# Ethernet.net
KiCad netlist of a schematic drawn in Altium Designer
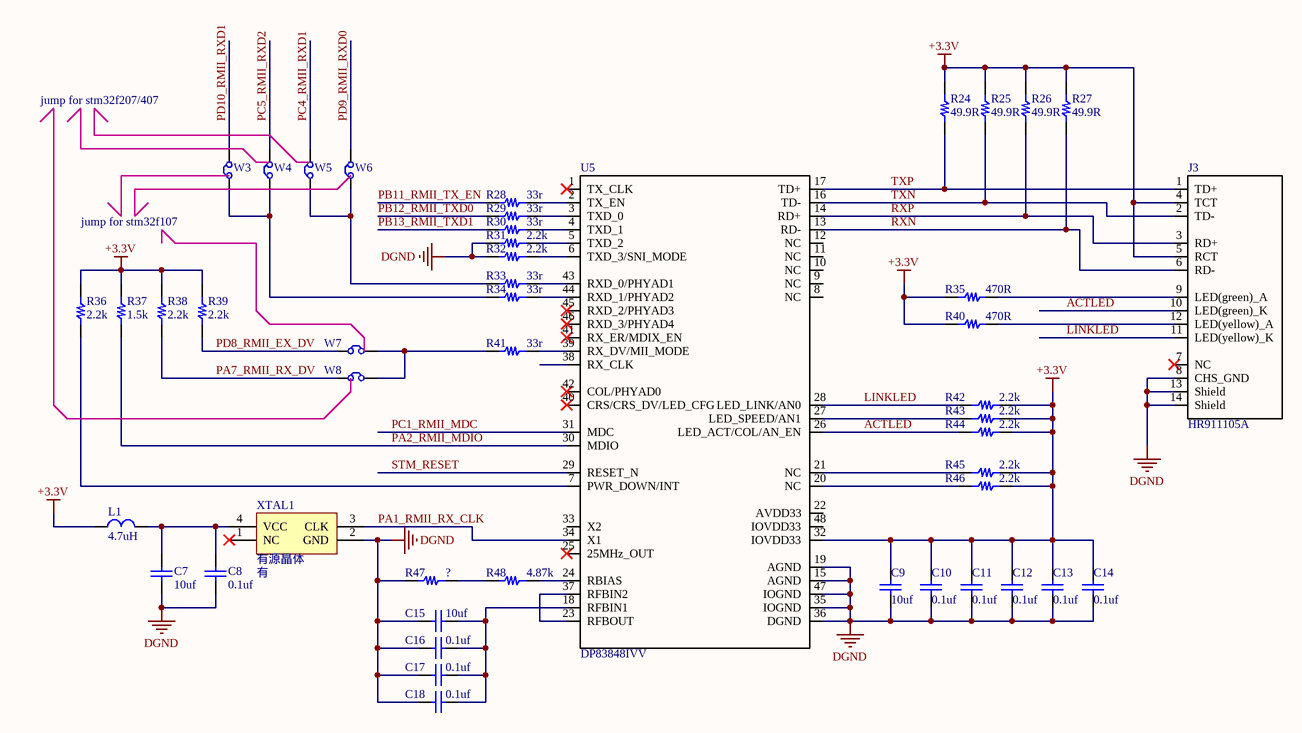
[diagram p0: Ethernet.SchDoc]

(export (version "E")
  (design (tool "Eeschema 10.0.6"))
  (components
    (comp (ref "C7")
      (value "10uf")
      (footprint "0805C")
      (description "贴片电容")
      (fields (field (name "PUBLISHER") "Altium Limited"))
      (libsource (lib "Device_CHT") (part "Cap"))
    )
    (comp (ref "C8")
      (value "0.1uf")
      (footprint "0805C")
      (description "贴片电容")
      (fields (field (name "PUBLISHER") "Altium Limited"))
      (libsource (lib "Device_CHT") (part "Cap"))
    )
    (comp (ref "C9")
      (value "10uf")
      (footprint "0805C")
      (description "贴片电容")
      (fields (field (name "PUBLISHER") "Altium Limited"))
      (libsource (lib "Device_CHT") (part "Cap"))
    )
    (comp (ref "C10")
      (value "0.1uf")
      (footprint "0805C")
      (description "贴片电容")
      (fields (field (name "PUBLISHER") "Altium Limited"))
      (libsource (lib "Device_CHT") (part "Cap"))
    )
    (comp (ref "C11")
      (value "0.1uf")
      (footprint "0805C")
      (description "贴片电容")
      (fields (field (name "PUBLISHER") "Altium Limited"))
      (libsource (lib "Device_CHT") (part "Cap"))
    )
    (comp (ref "C12")
      (value "0.1uf")
      (footprint "0805C")
      (description "贴片电容")
      (fields (field (name "PUBLISHER") "Altium Limited"))
      (libsource (lib "Device_CHT") (part "Cap"))
    )
    (comp (ref "C13")
      (value "0.1uf")
      (footprint "0805C")
      (description "贴片电容")
      (fields (field (name "PUBLISHER") "Altium Limited"))
      (libsource (lib "Device_CHT") (part "Cap"))
    )
    (comp (ref "C14")
      (value "0.1uf")
      (footprint "0805C")
      (description "贴片电容")
      (fields (field (name "PUBLISHER") "Altium Limited"))
      (libsource (lib "Device_CHT") (part "Cap"))
    )
    (comp (ref "C15")
      (value "10uf")
      (footprint "0805C")
      (description "贴片电容")
      (fields (field (name "PUBLISHER") "Altium Limited"))
      (libsource (lib "Device_CHT") (part "Cap"))
    )
    (comp (ref "C16")
      (value "0.1uf")
      (footprint "0805C")
      (description "贴片电容")
      (fields (field (name "PUBLISHER") "Altium Limited"))
      (libsource (lib "Device_CHT") (part "Cap"))
    )
    (comp (ref "C17")
      (value "0.1uf")
      (footprint "0805C")
      (description "贴片电容")
      (fields (field (name "PUBLISHER") "Altium Limited"))
      (libsource (lib "Device_CHT") (part "Cap"))
    )
    (comp (ref "C18")
      (value "0.1uf")
      (footprint "0805C")
      (description "贴片电容")
      (fields (field (name "PUBLISHER") "Altium Limited"))
      (libsource (lib "Device_CHT") (part "Cap"))
    )
    (comp (ref "J3")
      (value "HR911105A")
      (footprint "RJ45-HR911105A")
      (description "带网络变压器的网络接口")
      (libsource (lib "Connector_Veiko") (part "HR911105A"))
    )
    (comp (ref "L1")
      (value "4.7uH")
      (footprint "0805_SmallR")
      (description "电感")
      (fields (field (name "PUBLISHER") "Altium Limited"))
      (libsource (lib "Device_CHT") (part "Inductor"))
    )
    (comp (ref "R24")
      (value "49.9R")
      (footprint "0805_small")
      (description "电阻")
      (fields (field (name "PUBLISHER") "Altium Limited"))
      (libsource (lib "Device_CHT") (part "Res"))
    )
    (comp (ref "R25")
      (value "49.9R")
      (footprint "0805_small")
      (description "电阻")
      (fields (field (name "PUBLISHER") "Altium Limited"))
      (libsource (lib "Device_CHT") (part "Res"))
    )
    (comp (ref "R26")
      (value "49.9R")
      (footprint "0805_small")
      (description "电阻")
      (fields (field (name "PUBLISHER") "Altium Limited"))
      (libsource (lib "Device_CHT") (part "Res"))
    )
    (comp (ref "R27")
      (value "49.9R")
      (footprint "0805_small")
      (description "电阻")
      (fields (field (name "PUBLISHER") "Altium Limited"))
      (libsource (lib "Device_CHT") (part "Res"))
    )
    (comp (ref "R28")
      (value "33r")
      (footprint "0805_small")
      (description "电阻")
      (fields (field (name "PUBLISHER") "Altium Limited"))
      (libsource (lib "Device_CHT") (part "Res"))
    )
    (comp (ref "R29")
      (value "33r")
      (footprint "0805_small")
      (description "电阻")
      (fields (field (name "PUBLISHER") "Altium Limited"))
      (libsource (lib "Device_CHT") (part "Res"))
    )
    (comp (ref "R30")
      (value "33r")
      (footprint "0805_small")
      (description "电阻")
      (fields (field (name "PUBLISHER") "Altium Limited"))
      (libsource (lib "Device_CHT") (part "Res"))
    )
    (comp (ref "R31")
      (value "2.2k")
      (footprint "0805_small")
      (description "电阻")
      (fields (field (name "PUBLISHER") "Altium Limited"))
      (libsource (lib "Device_CHT") (part "Res"))
    )
    (comp (ref "R32")
      (value "2.2k")
      (footprint "0805_small")
      (description "电阻")
      (fields (field (name "PUBLISHER") "Altium Limited"))
      (libsource (lib "Device_CHT") (part "Res"))
    )
    (comp (ref "R33")
      (value "33r")
      (footprint "0805_small")
      (description "电阻")
      (fields (field (name "PUBLISHER") "Altium Limited"))
      (libsource (lib "Device_CHT") (part "Res"))
    )
    (comp (ref "R34")
      (value "33r")
      (footprint "0805_small")
      (description "电阻")
      (fields (field (name "PUBLISHER") "Altium Limited"))
      (libsource (lib "Device_CHT") (part "Res"))
    )
    (comp (ref "R35")
      (value "470R")
      (footprint "0805_small")
      (description "电阻")
      (fields (field (name "PUBLISHER") "Altium Limited"))
      (libsource (lib "Device_CHT") (part "Res"))
    )
    (comp (ref "R36")
      (value "2.2k")
      (footprint "0805_small")
      (description "电阻")
      (fields (field (name "PUBLISHER") "Altium Limited"))
      (libsource (lib "Device_CHT") (part "Res"))
    )
    (comp (ref "R37")
      (value "1.5k")
      (footprint "0805_small")
      (description "电阻")
      (fields (field (name "PUBLISHER") "Altium Limited"))
      (libsource (lib "Device_CHT") (part "Res"))
    )
    (comp (ref "R38")
      (value "2.2k")
      (footprint "0805_small")
      (description "电阻")
      (fields (field (name "PUBLISHER") "Altium Limited"))
      (libsource (lib "Device_CHT") (part "Res"))
    )
    (comp (ref "R39")
      (value "2.2k")
      (footprint "0805_small")
      (description "电阻")
      (fields (field (name "PUBLISHER") "Altium Limited"))
      (libsource (lib "Device_CHT") (part "Res"))
    )
    (comp (ref "R40")
      (value "470R")
      (footprint "0805_small")
      (description "电阻")
      (fields (field (name "PUBLISHER") "Altium Limited"))
      (libsource (lib "Device_CHT") (part "Res"))
    )
    (comp (ref "R41")
      (value "33r")
      (footprint "0805_small")
      (description "电阻")
      (fields (field (name "PUBLISHER") "Altium Limited"))
      (libsource (lib "Device_CHT") (part "Res"))
    )
    (comp (ref "R42")
      (value "2.2k")
      (footprint "0805_small")
      (description "电阻")
      (fields (field (name "PUBLISHER") "Altium Limited"))
      (libsource (lib "Device_CHT") (part "Res"))
    )
    (comp (ref "R43")
      (value "2.2k")
      (footprint "0805_small")
      (description "电阻")
      (fields (field (name "PUBLISHER") "Altium Limited"))
      (libsource (lib "Device_CHT") (part "Res"))
    )
    (comp (ref "R44")
      (value "2.2k")
      (footprint "0805_small")
      (description "电阻")
      (fields (field (name "PUBLISHER") "Altium Limited"))
      (libsource (lib "Device_CHT") (part "Res"))
    )
    (comp (ref "R45")
      (value "2.2k")
      (footprint "0805_small")
      (description "电阻")
      (fields (field (name "PUBLISHER") "Altium Limited"))
      (libsource (lib "Device_CHT") (part "Res"))
    )
    (comp (ref "R46")
      (value "2.2k")
      (footprint "0805_small")
      (description "电阻")
      (fields (field (name "PUBLISHER") "Altium Limited"))
      (libsource (lib "Device_CHT") (part "Res"))
    )
    (comp (ref "R47")
      (value "?")
      (footprint "0805_small")
      (description "电阻")
      (fields (field (name "PUBLISHER") "Altium Limited"))
      (libsource (lib "Device_CHT") (part "Res"))
    )
    (comp (ref "R48")
      (value "4.87k")
      (footprint "0805_small")
      (description "电阻")
      (fields (field (name "PUBLISHER") "Altium Limited"))
      (libsource (lib "Device_CHT") (part "Res"))
    )
    (comp (ref "U5")
      (value "DP83848IVV")
      (footprint "LQFP-48")
      (description "DP83848 PHY")
      (libsource (lib "Device_CHT") (part "DP83848IVV"))
    )
    (comp (ref "W3")
      (value "~")
      (footprint "0603_jump_Pad")
      (description "Jumper Wire")
      (fields (field (name "PUBLISHER") "Altium Limited"))
      (libsource (lib "Connector_Veiko") (part "Jumper"))
    )
    (comp (ref "W4")
      (value "~")
      (footprint "0603_jump_Pad")
      (description "Jumper Wire")
      (fields (field (name "PUBLISHER") "Altium Limited"))
      (libsource (lib "Connector_Veiko") (part "Jumper"))
    )
    (comp (ref "W5")
      (value "~")
      (footprint "0603_jump_Pad")
      (description "Jumper Wire")
      (fields (field (name "PUBLISHER") "Altium Limited"))
      (libsource (lib "Connector_Veiko") (part "Jumper"))
    )
    (comp (ref "W6")
      (value "~")
      (footprint "0603_jump_Pad")
      (description "Jumper Wire")
      (fields (field (name "PUBLISHER") "Altium Limited"))
      (libsource (lib "Connector_Veiko") (part "Jumper"))
    )
    (comp (ref "W7")
      (value "~")
      (footprint "0603_jump_Pad")
      (description "Jumper Wire")
      (fields (field (name "PUBLISHER") "Altium Limited"))
      (libsource (lib "Connector_Veiko") (part "Jumper"))
    )
    (comp (ref "W8")
      (value "~")
      (footprint "0603_jump_Pad")
      (description "Jumper Wire")
      (fields (field (name "PUBLISHER") "Altium Limited"))
      (libsource (lib "Connector_Veiko") (part "Jumper"))
    )
    (comp (ref "XTAL1")
      (value "有源晶体")
      (footprint "贴片有源晶体")
      (fields (field (name "ALTIUM_UNNAMED_1") "有"))
      (libsource (lib "Device_CHT") (part "有源晶体"))
    )
  )
  (nets
    (net (code "1") (name "+3.3V") (class "Default")
      (node (ref "C10") (pin "1") (pinfunction "1_1") (pintype "passive"))
      (node (ref "C11") (pin "1") (pinfunction "1_1") (pintype "passive"))
      (node (ref "C12") (pin "1") (pinfunction "1_1") (pintype "passive"))
      (node (ref "C13") (pin "1") (pinfunction "1_1") (pintype "passive"))
      (node (ref "C14") (pin "1") (pinfunction "1_1") (pintype "passive"))
      (node (ref "C9") (pin "1") (pinfunction "1_1") (pintype "passive"))
      (node (ref "J3") (pin "4") (pinfunction "TCT_4") (pintype "passive"))
      (node (ref "J3") (pin "5") (pinfunction "RCT_5") (pintype "passive"))
      (node (ref "L1") (pin "1") (pinfunction "1_1") (pintype "passive"))
      (node (ref "R24") (pin "1") (pinfunction "1_1") (pintype "passive"))
      (node (ref "R25") (pin "1") (pinfunction "1_1") (pintype "passive"))
      (node (ref "R26") (pin "1") (pinfunction "1_1") (pintype "passive"))
      (node (ref "R27") (pin "1") (pinfunction "1_1") (pintype "passive"))
      (node (ref "R35") (pin "1") (pinfunction "1_1") (pintype "passive"))
      (node (ref "R36") (pin "1") (pinfunction "1_1") (pintype "passive"))
      (node (ref "R37") (pin "1") (pinfunction "1_1") (pintype "passive"))
      (node (ref "R38") (pin "1") (pinfunction "1_1") (pintype "passive"))
      (node (ref "R39") (pin "1") (pinfunction "1_1") (pintype "passive"))
      (node (ref "R40") (pin "1") (pinfunction "1_1") (pintype "passive"))
      (node (ref "R42") (pin "2") (pinfunction "2_2") (pintype "passive"))
      (node (ref "R43") (pin "2") (pinfunction "2_2") (pintype "passive"))
      (node (ref "R44") (pin "2") (pinfunction "2_2") (pintype "passive"))
      (node (ref "R45") (pin "2") (pinfunction "2_2") (pintype "passive"))
      (node (ref "R46") (pin "2") (pinfunction "2_2") (pintype "passive"))
      (node (ref "U5") (pin "32") (pinfunction "IOVDD33_32") (pintype "passive"))
    )
    (net (code "2") (name "/ACTLED") (class "Default")
      (node (ref "J3") (pin "10") (pinfunction "LED(green)_K_10") (pintype "passive"))
      (node (ref "R44") (pin "1") (pinfunction "1_1") (pintype "passive"))
      (node (ref "U5") (pin "26") (pinfunction "LED_ACT/COL/AN_EN_26") (pintype "passive"))
    )
    (net (code "3") (name "/LINKLED") (class "Default")
      (node (ref "J3") (pin "11") (pinfunction "LED(yellow)_K_11") (pintype "passive"))
      (node (ref "R42") (pin "1") (pinfunction "1_1") (pintype "passive"))
      (node (ref "U5") (pin "28") (pinfunction "LED_LINK/AN0_28") (pintype "passive"))
    )
    (net (code "4") (name "/PA1_RMII_RX_CLK") (class "Default")
      (node (ref "U5") (pin "34") (pinfunction "X1_34") (pintype "passive"))
      (node (ref "XTAL1") (pin "3") (pinfunction "CLK_3") (pintype "passive"))
    )
    (net (code "5") (name "/PA2_RMII_MDIO") (class "Default")
      (node (ref "R37") (pin "2") (pinfunction "2_2") (pintype "passive"))
      (node (ref "U5") (pin "30") (pinfunction "MDIO_30") (pintype "passive"))
    )
    (net (code "6") (name "/PA7_RMII_RX_DV") (class "Default")
      (node (ref "R38") (pin "2") (pinfunction "2_2") (pintype "passive"))
      (node (ref "W8") (pin "1") (pinfunction "C1_1") (pintype "passive"))
    )
    (net (code "7") (name "/PB11_RMII_TX_EN") (class "Default")
      (node (ref "R28") (pin "2") (pinfunction "2_2") (pintype "passive"))
    )
    (net (code "8") (name "/PB12_RMII_TXD0") (class "Default")
      (node (ref "R29") (pin "2") (pinfunction "2_2") (pintype "passive"))
    )
    (net (code "9") (name "/PB13_RMII_TXD1") (class "Default")
      (node (ref "R30") (pin "2") (pinfunction "2_2") (pintype "passive"))
    )
    (net (code "10") (name "/PC1_RMII_MDC") (class "Default")
      (node (ref "U5") (pin "31") (pinfunction "MDC_31") (pintype "passive"))
    )
    (net (code "11") (name "/PC4_RMII_RXD1") (class "Default")
      (node (ref "W5") (pin "2") (pinfunction "C2_2") (pintype "passive"))
    )
    (net (code "12") (name "/PC5_RMII_RXD2") (class "Default")
      (node (ref "W4") (pin "2") (pinfunction "C2_2") (pintype "passive"))
    )
    (net (code "13") (name "/PD8_RMII_EX_DV") (class "Default")
      (node (ref "R39") (pin "2") (pinfunction "2_2") (pintype "passive"))
      (node (ref "W7") (pin "1") (pinfunction "C1_1") (pintype "passive"))
    )
    (net (code "14") (name "/PD9_RMII_RXD0") (class "Default")
      (node (ref "W6") (pin "2") (pinfunction "C2_2") (pintype "passive"))
    )
    (net (code "15") (name "/PD10_RMII_RXD1") (class "Default")
      (node (ref "W3") (pin "2") (pinfunction "C2_2") (pintype "passive"))
    )
    (net (code "16") (name "/RXN") (class "Default")
      (node (ref "J3") (pin "6") (pinfunction "RD-_6") (pintype "passive"))
      (node (ref "R27") (pin "2") (pinfunction "2_2") (pintype "passive"))
      (node (ref "U5") (pin "13") (pinfunction "RD-_13") (pintype "passive"))
    )
    (net (code "17") (name "/RXP") (class "Default")
      (node (ref "J3") (pin "3") (pinfunction "RD+_3") (pintype "passive"))
      (node (ref "R26") (pin "2") (pinfunction "2_2") (pintype "passive"))
      (node (ref "U5") (pin "14") (pinfunction "RD+_14") (pintype "passive"))
    )
    (net (code "18") (name "/STM_RESET") (class "Default")
      (node (ref "U5") (pin "29") (pinfunction "RESET_N_29") (pintype "passive"))
    )
    (net (code "19") (name "/TXN") (class "Default")
      (node (ref "J3") (pin "2") (pinfunction "TD-_2") (pintype "passive"))
      (node (ref "R25") (pin "2") (pinfunction "2_2") (pintype "passive"))
      (node (ref "U5") (pin "16") (pinfunction "TD-_16") (pintype "passive"))
    )
    (net (code "20") (name "/TXP") (class "Default")
      (node (ref "J3") (pin "1") (pinfunction "TD+_1") (pintype "passive"))
      (node (ref "R24") (pin "2") (pinfunction "2_2") (pintype "passive"))
      (node (ref "U5") (pin "17") (pinfunction "TD+_17") (pintype "passive"))
    )
    (net (code "21") (name "DGND") (class "Default")
      (node (ref "C10") (pin "2") (pinfunction "2_2") (pintype "passive"))
      (node (ref "C11") (pin "2") (pinfunction "2_2") (pintype "passive"))
      (node (ref "C12") (pin "2") (pinfunction "2_2") (pintype "passive"))
      (node (ref "C13") (pin "2") (pinfunction "2_2") (pintype "passive"))
      (node (ref "C14") (pin "2") (pinfunction "2_2") (pintype "passive"))
      (node (ref "C15") (pin "2") (pinfunction "2_2") (pintype "passive"))
      (node (ref "C16") (pin "2") (pinfunction "2_2") (pintype "passive"))
      (node (ref "C17") (pin "2") (pinfunction "2_2") (pintype "passive"))
      (node (ref "C18") (pin "2") (pinfunction "2_2") (pintype "passive"))
      (node (ref "C7") (pin "2") (pinfunction "2_2") (pintype "passive"))
      (node (ref "C8") (pin "2") (pinfunction "2_2") (pintype "passive"))
      (node (ref "C9") (pin "2") (pinfunction "2_2") (pintype "passive"))
      (node (ref "J3") (pin "13") (pinfunction "Shield_13") (pintype "passive"))
      (node (ref "J3") (pin "14") (pinfunction "Shield_14") (pintype "passive"))
      (node (ref "J3") (pin "8") (pinfunction "CHS_GND_8") (pintype "passive"))
      (node (ref "R31") (pin "2") (pinfunction "2_2") (pintype "passive"))
      (node (ref "R32") (pin "2") (pinfunction "2_2") (pintype "passive"))
      (node (ref "R47") (pin "2") (pinfunction "2_2") (pintype "passive"))
      (node (ref "U5") (pin "15") (pinfunction "AGND_15") (pintype "passive"))
      (node (ref "U5") (pin "19") (pinfunction "AGND_19") (pintype "passive"))
      (node (ref "U5") (pin "35") (pinfunction "IOGND_35") (pintype "passive"))
      (node (ref "U5") (pin "36") (pinfunction "DGND_36") (pintype "passive"))
      (node (ref "U5") (pin "47") (pinfunction "IOGND_47") (pintype "passive"))
      (node (ref "XTAL1") (pin "2") (pinfunction "GND_2") (pintype "passive"))
    )
    (net (code "22") (name "Net-(J3-LED(green)_A)") (class "Default")
      (node (ref "J3") (pin "9") (pinfunction "LED(green)_A_9") (pintype "passive"))
      (node (ref "R35") (pin "2") (pinfunction "2_2") (pintype "passive"))
    )
    (net (code "23") (name "Net-(J3-LED(yellow)_A)") (class "Default")
      (node (ref "J3") (pin "12") (pinfunction "LED(yellow)_A_12") (pintype "passive"))
      (node (ref "R40") (pin "2") (pinfunction "2_2") (pintype "passive"))
    )
    (net (code "24") (name "Net-(R45-Pad1)") (class "Default")
      (node (ref "R45") (pin "1") (pinfunction "1_1") (pintype "passive"))
      (node (ref "U5") (pin "21") (pinfunction "NC_21") (pintype "passive"))
    )
    (net (code "25") (name "Net-(R46-Pad1)") (class "Default")
      (node (ref "R46") (pin "1") (pinfunction "1_1") (pintype "passive"))
      (node (ref "U5") (pin "20") (pinfunction "NC_20") (pintype "passive"))
    )
    (net (code "26") (name "Net-(R47-Pad1)") (class "Default")
      (node (ref "R47") (pin "1") (pinfunction "1_1") (pintype "passive"))
      (node (ref "R48") (pin "2") (pinfunction "2_2") (pintype "passive"))
    )
    (net (code "27") (name "Net-(U5-LED_SPEED{slash}AN1)") (class "Default")
      (node (ref "R43") (pin "1") (pinfunction "1_1") (pintype "passive"))
      (node (ref "U5") (pin "27") (pinfunction "LED_SPEED/AN1_27") (pintype "passive"))
    )
    (net (code "28") (name "Net-(U5-PWR_DOWN{slash}INT)") (class "Default")
      (node (ref "R36") (pin "2") (pinfunction "2_2") (pintype "passive"))
      (node (ref "U5") (pin "7") (pinfunction "PWR_DOWN/INT_7") (pintype "passive"))
    )
    (net (code "29") (name "Net-(U5-RBIAS)") (class "Default")
      (node (ref "R48") (pin "1") (pinfunction "1_1") (pintype "passive"))
      (node (ref "U5") (pin "24") (pinfunction "RBIAS_24") (pintype "passive"))
    )
    (net (code "30") (name "Net-(U5-RFBIN1)") (class "Default")
      (node (ref "C15") (pin "1") (pinfunction "1_1") (pintype "passive"))
      (node (ref "C16") (pin "1") (pinfunction "1_1") (pintype "passive"))
      (node (ref "C17") (pin "1") (pinfunction "1_1") (pintype "passive"))
      (node (ref "C18") (pin "1") (pinfunction "1_1") (pintype "passive"))
      (node (ref "U5") (pin "18") (pinfunction "RFBIN1_18") (pintype "passive"))
    )
    (net (code "31") (name "Net-(U5-RFBIN2)") (class "Default")
      (node (ref "U5") (pin "23") (pinfunction "RFBOUT_23") (pintype "passive"))
      (node (ref "U5") (pin "37") (pinfunction "RFBIN2_37") (pintype "passive"))
    )
    (net (code "32") (name "Net-(U5-RXD_0{slash}PHYAD1)") (class "Default")
      (node (ref "R33") (pin "1") (pinfunction "1_1") (pintype "passive"))
      (node (ref "U5") (pin "43") (pinfunction "RXD_0/PHYAD1_43") (pintype "passive"))
    )
    (net (code "33") (name "Net-(U5-RXD_1{slash}PHYAD2)") (class "Default")
      (node (ref "R34") (pin "1") (pinfunction "1_1") (pintype "passive"))
      (node (ref "U5") (pin "44") (pinfunction "RXD_1/PHYAD2_44") (pintype "passive"))
    )
    (net (code "34") (name "Net-(U5-RX_DV{slash}MII_MODE)") (class "Default")
      (node (ref "R41") (pin "1") (pinfunction "1_1") (pintype "passive"))
      (node (ref "U5") (pin "39") (pinfunction "RX_DV/MII_MODE_39") (pintype "passive"))
    )
    (net (code "35") (name "Net-(U5-TXD_0)") (class "Default")
      (node (ref "R29") (pin "1") (pinfunction "1_1") (pintype "passive"))
      (node (ref "U5") (pin "3") (pinfunction "TXD_0_3") (pintype "passive"))
    )
    (net (code "36") (name "Net-(U5-TXD_1)") (class "Default")
      (node (ref "R30") (pin "1") (pinfunction "1_1") (pintype "passive"))
      (node (ref "U5") (pin "4") (pinfunction "TXD_1_4") (pintype "passive"))
    )
    (net (code "37") (name "Net-(U5-TXD_2)") (class "Default")
      (node (ref "R31") (pin "1") (pinfunction "1_1") (pintype "passive"))
      (node (ref "U5") (pin "5") (pinfunction "TXD_2_5") (pintype "passive"))
    )
    (net (code "38") (name "Net-(U5-TXD_3{slash}SNI_MODE)") (class "Default")
      (node (ref "R32") (pin "1") (pinfunction "1_1") (pintype "passive"))
      (node (ref "U5") (pin "6") (pinfunction "TXD_3/SNI_MODE_6") (pintype "passive"))
    )
    (net (code "39") (name "Net-(U5-TX_EN)") (class "Default")
      (node (ref "R28") (pin "1") (pinfunction "1_1") (pintype "passive"))
      (node (ref "U5") (pin "2") (pinfunction "TX_EN_2") (pintype "passive"))
    )
    (net (code "40") (name "Net-(W3-C1)") (class "Default")
      (node (ref "R34") (pin "2") (pinfunction "2_2") (pintype "passive"))
      (node (ref "W3") (pin "1") (pinfunction "C1_1") (pintype "passive"))
      (node (ref "W4") (pin "1") (pinfunction "C1_1") (pintype "passive"))
    )
    (net (code "41") (name "Net-(W5-C1)") (class "Default")
      (node (ref "R33") (pin "2") (pinfunction "2_2") (pintype "passive"))
      (node (ref "W5") (pin "1") (pinfunction "C1_1") (pintype "passive"))
      (node (ref "W6") (pin "1") (pinfunction "C1_1") (pintype "passive"))
    )
    (net (code "42") (name "Net-(W7-C2)") (class "Default")
      (node (ref "R41") (pin "2") (pinfunction "2_2") (pintype "passive"))
      (node (ref "W7") (pin "2") (pinfunction "C2_2") (pintype "passive"))
      (node (ref "W8") (pin "2") (pinfunction "C2_2") (pintype "passive"))
    )
    (net (code "43") (name "Net-(XTAL1-VCC)") (class "Default")
      (node (ref "C7") (pin "1") (pinfunction "1_1") (pintype "passive"))
      (node (ref "C8") (pin "1") (pinfunction "1_1") (pintype "passive"))
      (node (ref "L1") (pin "2") (pinfunction "2_2") (pintype "passive"))
      (node (ref "XTAL1") (pin "4") (pinfunction "VCC_4") (pintype "passive"))
    )
    (net (code "44") (name "unconnected-(J3-NC-Pad7)") (class "Default")
      (node (ref "J3") (pin "7") (pinfunction "NC_7") (pintype "passive+no_connect"))
    )
    (net (code "45") (name "unconnected-(U5-25MHz_OUT-Pad25)") (class "Default")
      (node (ref "U5") (pin "25") (pinfunction "25MHz_OUT_25") (pintype "passive+no_connect"))
    )
    (net (code "46") (name "unconnected-(U5-AVDD33-Pad22)") (class "Default")
      (node (ref "U5") (pin "22") (pinfunction "AVDD33_22") (pintype "passive"))
    )
    (net (code "47") (name "unconnected-(U5-COL{slash}PHYAD0-Pad42)") (class "Default")
      (node (ref "U5") (pin "42") (pinfunction "COL/PHYAD0_42") (pintype "passive+no_connect"))
    )
    (net (code "48") (name "unconnected-(U5-CRS{slash}CRS_DV{slash}LED_CFG-Pad40)") (class "Default")
      (node (ref "U5") (pin "40") (pinfunction "CRS/CRS_DV/LED_CFG_40") (pintype "passive+no_connect"))
    )
    (net (code "49") (name "unconnected-(U5-IOVDD33-Pad48)") (class "Default")
      (node (ref "U5") (pin "48") (pinfunction "IOVDD33_48") (pintype "passive"))
    )
    (net (code "50") (name "unconnected-(U5-NC-Pad8)") (class "Default")
      (node (ref "U5") (pin "8") (pinfunction "NC_8") (pintype "passive"))
    )
    (net (code "51") (name "unconnected-(U5-NC-Pad9)") (class "Default")
      (node (ref "U5") (pin "9") (pinfunction "NC_9") (pintype "passive"))
    )
    (net (code "52") (name "unconnected-(U5-NC-Pad10)") (class "Default")
      (node (ref "U5") (pin "10") (pinfunction "NC_10") (pintype "passive"))
    )
    (net (code "53") (name "unconnected-(U5-NC-Pad11)") (class "Default")
      (node (ref "U5") (pin "11") (pinfunction "NC_11") (pintype "passive"))
    )
    (net (code "54") (name "unconnected-(U5-NC-Pad12)") (class "Default")
      (node (ref "U5") (pin "12") (pinfunction "NC_12") (pintype "passive"))
    )
    (net (code "55") (name "unconnected-(U5-RXD_2{slash}PHYAD3-Pad45)") (class "Default")
      (node (ref "U5") (pin "45") (pinfunction "RXD_2/PHYAD3_45") (pintype "passive+no_connect"))
    )
    (net (code "56") (name "unconnected-(U5-RXD_3{slash}PHYAD4-Pad46)") (class "Default")
      (node (ref "U5") (pin "46") (pinfunction "RXD_3/PHYAD4_46") (pintype "passive+no_connect"))
    )
    (net (code "57") (name "unconnected-(U5-RX_CLK-Pad38)") (class "Default")
      (node (ref "U5") (pin "38") (pinfunction "RX_CLK_38") (pintype "passive"))
    )
    (net (code "58") (name "unconnected-(U5-RX_ER{slash}MDIX_EN-Pad41)") (class "Default")
      (node (ref "U5") (pin "41") (pinfunction "RX_ER/MDIX_EN_41") (pintype "passive+no_connect"))
    )
    (net (code "59") (name "unconnected-(U5-TX_CLK-Pad1)") (class "Default")
      (node (ref "U5") (pin "1") (pinfunction "TX_CLK_1") (pintype "passive+no_connect"))
    )
    (net (code "60") (name "unconnected-(U5-X2-Pad33)") (class "Default")
      (node (ref "U5") (pin "33") (pinfunction "X2_33") (pintype "passive"))
    )
    (net (code "61") (name "unconnected-(XTAL1-NC-Pad1)") (class "Default")
      (node (ref "XTAL1") (pin "1") (pinfunction "NC_1") (pintype "passive+no_connect"))
    )
  )
)
